# 05_LMS7002M_Misc.net
KiCad netlist of a schematic drawn in Altium Designer
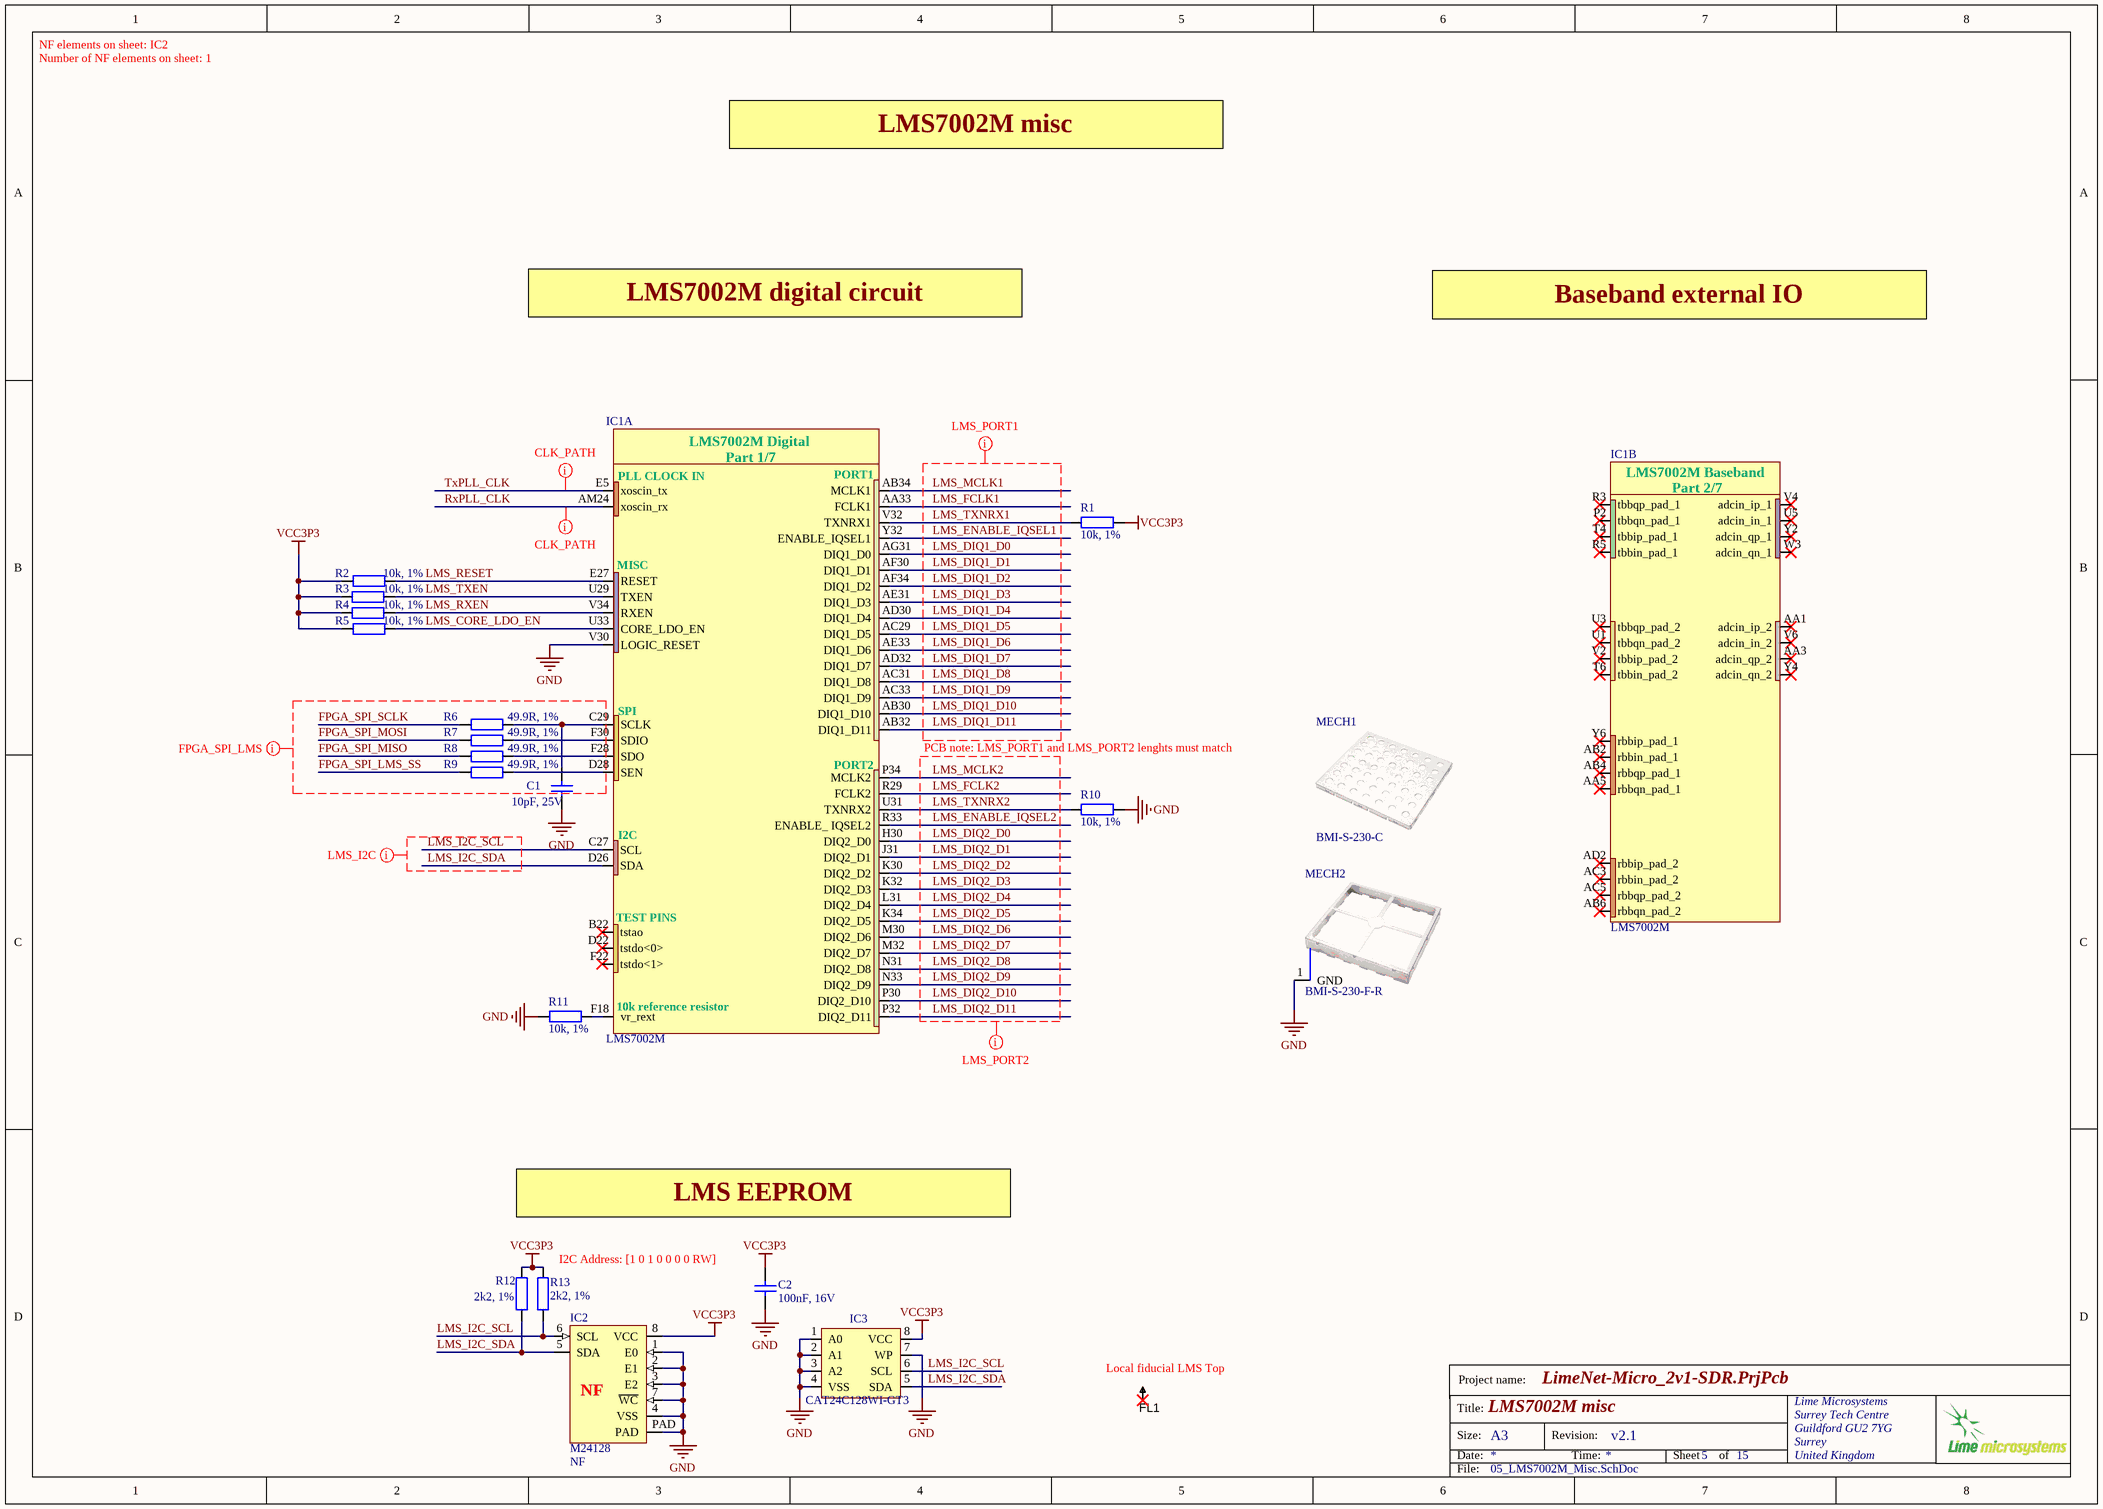
[diagram p0: 05_LMS7002M_Misc.SchDoc]

(export (version "E")
  (design (tool "Eeschema 10.0.6"))
  (components
    (comp (ref "C1")
      (value "10pF, 25V")
      (footprint "CAP0402")
      (fields (field (name "MANUFACTURER") "AVX"))
      (libsource (lib "LimeMicroAltiumLib_schLib") (part "Cap_0402"))
    )
    (comp (ref "C2")
      (value "100nF, 16V")
      (footprint "CAP0402")
      (fields (field (name "TOLERANCE") "10 %") (field (name "MANUFACTURER") "Murata Electronics"))
      (libsource (lib "LimeFPGAboard_schLib") (part "Cap_0603"))
    )
    (comp (ref "FL1")
      (value "Fiducial")
      (footprint "Fiducial_local")
      (libsource (lib "VGTU_Altium_lib") (part "Fiducial"))
    )
    (comp (ref "IC1")
      (value "LMS7002M")
      (footprint "LMS7002M_v5")
      (description "Schematic symbol revision 3. Default footprint - 0.31mm pad")
      (fields (field (name "MANUFACTURER") "Lime Microsystems"))
      (libsource (lib "LimeMicroAltiumLib_schLib") (part "LMS7002Mr3"))
    )
    (comp (ref "IC2")
      (value "M24128")
      (footprint "M24128-DFMC6TG")
      (fields (field (name "MANUFACTURER") "STMicroelectronics") (field (name "ASSEMBLY INFO") "NF"))
      (libsource (lib "LimeMicroAltiumLib_schLib") (part "M24128-DFMC6TG"))
    )
    (comp (ref "IC3")
      (value "CAT24C128WI-GT3")
      (footprint "SOIC127P600-8DL_v2")
      (fields (field (name "MANUFACTURER") "ON Semiconductor") (field (name "BASE PART NUMBER") "CAT24C128"))
      (libsource (lib "LimeMicroAltiumLib_schLib") (part "24FC64F"))
    )
    (comp (ref "MECH1")
      (value "BMI-S-230-C")
      (fields (field (name "MANUFACTURER") "Laird Technologies EMI"))
      (libsource (lib "LimeMicroAltiumLib_schLib_r01") (part "RFI_SHIELD_2_cover"))
    )
    (comp (ref "MECH2")
      (value "BMI-S-230-F-R")
      (footprint "RFI_SHIELD_BMI-S-230-F-R")
      (fields (field (name "MANUFACTURER") "Laird Technologies EMI"))
      (libsource (lib "LimeMicroAltiumLib_schLib_r01") (part "RFI_SHIELD_2_frame"))
    )
    (comp (ref "R1")
      (value "10k, 1%")
      (footprint "RES0402")
      (fields (field (name "MANUFACTURER") "Yageo") (field (name "TOLERANCE") "±1%"))
      (libsource (lib "LimeMicroAltiumLib_schLib") (part "Res_0402"))
    )
    (comp (ref "R2")
      (value "10k, 1%")
      (footprint "RES0402")
      (fields (field (name "MANUFACTURER") "Yageo") (field (name "TOLERANCE") "±1%"))
      (libsource (lib "LimeMicroAltiumLib_schLib") (part "Res_0402"))
    )
    (comp (ref "R3")
      (value "10k, 1%")
      (footprint "RES0402")
      (fields (field (name "MANUFACTURER") "Yageo") (field (name "TOLERANCE") "±1%"))
      (libsource (lib "LimeMicroAltiumLib_schLib") (part "Res_0402"))
    )
    (comp (ref "R4")
      (value "10k, 1%")
      (footprint "RES0402")
      (fields (field (name "MANUFACTURER") "Yageo") (field (name "TOLERANCE") "±1%"))
      (libsource (lib "LimeMicroAltiumLib_schLib") (part "Res_0402"))
    )
    (comp (ref "R5")
      (value "10k, 1%")
      (footprint "RES0402")
      (fields (field (name "MANUFACTURER") "Yageo") (field (name "TOLERANCE") "±1%"))
      (libsource (lib "LimeMicroAltiumLib_schLib") (part "Res_0402"))
    )
    (comp (ref "R6")
      (value "49.9R, 1%")
      (footprint "RES0402")
      (fields
        (field (name "TOLERANCE") "±1%")
        (field (name "MANUFACTURER") "Samsung Electro-Mechanics America, Inc.")
      )
      (libsource (lib "LimeMicroAltiumLib_schLib") (part "Res_0402"))
    )
    (comp (ref "R7")
      (value "49.9R, 1%")
      (footprint "RES0402")
      (fields
        (field (name "TOLERANCE") "±1%")
        (field (name "MANUFACTURER") "Samsung Electro-Mechanics America, Inc.")
      )
      (libsource (lib "LimeMicroAltiumLib_schLib") (part "Res_0402"))
    )
    (comp (ref "R8")
      (value "49.9R, 1%")
      (footprint "RES0402")
      (fields
        (field (name "TOLERANCE") "±1%")
        (field (name "MANUFACTURER") "Samsung Electro-Mechanics America, Inc.")
      )
      (libsource (lib "LimeMicroAltiumLib_schLib") (part "Res_0402"))
    )
    (comp (ref "R9")
      (value "49.9R, 1%")
      (footprint "RES0402")
      (fields
        (field (name "TOLERANCE") "±1%")
        (field (name "MANUFACTURER") "Samsung Electro-Mechanics America, Inc.")
      )
      (libsource (lib "LimeMicroAltiumLib_schLib") (part "Res_0402"))
    )
    (comp (ref "R10")
      (value "10k, 1%")
      (footprint "RES0402")
      (fields (field (name "MANUFACTURER") "Yageo") (field (name "TOLERANCE") "±1%"))
      (libsource (lib "LimeMicroAltiumLib_schLib") (part "Res_0402"))
    )
    (comp (ref "R11")
      (value "10k, 1%")
      (footprint "RES0402")
      (fields (field (name "MANUFACTURER") "Yageo") (field (name "TOLERANCE") "±1%"))
      (libsource (lib "LimeMicroAltiumLib_schLib") (part "Res_0402"))
    )
    (comp (ref "R12")
      (value "2k2, 1%")
      (footprint "RES0402")
      (fields (field (name "MANUFACTURER") "Stackpole Electronics Inc") (field (name "TOLERANCE") "±1%"))
      (libsource (lib "LimeMicroAltiumLib_schLib") (part "Res_0402"))
    )
    (comp (ref "R13")
      (value "2k2, 1%")
      (footprint "RES0402")
      (fields (field (name "MANUFACTURER") "Stackpole Electronics Inc") (field (name "TOLERANCE") "±1%"))
      (libsource (lib "LimeMicroAltiumLib_schLib") (part "Res_0402"))
    )
  )
  (nets
    (net (code "1") (name "/FPGA_SPI_LMS_SS") (class "Default")
      (node (ref "R9") (pin "2") (pinfunction "2_2") (pintype "passive"))
    )
    (net (code "2") (name "/FPGA_SPI_MISO") (class "Default")
      (node (ref "R8") (pin "2") (pinfunction "2_2") (pintype "passive"))
    )
    (net (code "3") (name "/FPGA_SPI_MOSI") (class "Default")
      (node (ref "R7") (pin "2") (pinfunction "2_2") (pintype "passive"))
    )
    (net (code "4") (name "/FPGA_SPI_SCLK") (class "Default")
      (node (ref "R6") (pin "2") (pinfunction "2_2") (pintype "passive"))
    )
    (net (code "5") (name "/LMS_CORE_LDO_EN") (class "Default")
      (node (ref "IC1") (pin "U33") (pinfunction "CORE_LDO_EN_U33") (pintype "passive"))
      (node (ref "R5") (pin "1") (pinfunction "1_1") (pintype "passive"))
    )
    (net (code "6") (name "/LMS_DIQ1_D0") (class "Default")
      (node (ref "IC1") (pin "AG31") (pinfunction "DIQ1_D0_AG31") (pintype "passive"))
    )
    (net (code "7") (name "/LMS_DIQ1_D1") (class "Default")
      (node (ref "IC1") (pin "AF30") (pinfunction "DIQ1_D1_AF30") (pintype "passive"))
    )
    (net (code "8") (name "/LMS_DIQ1_D2") (class "Default")
      (node (ref "IC1") (pin "AF34") (pinfunction "DIQ1_D2_AF34") (pintype "passive"))
    )
    (net (code "9") (name "/LMS_DIQ1_D3") (class "Default")
      (node (ref "IC1") (pin "AE31") (pinfunction "DIQ1_D3_AE31") (pintype "passive"))
    )
    (net (code "10") (name "/LMS_DIQ1_D4") (class "Default")
      (node (ref "IC1") (pin "AD30") (pinfunction "DIQ1_D4_AD30") (pintype "passive"))
    )
    (net (code "11") (name "/LMS_DIQ1_D5") (class "Default")
      (node (ref "IC1") (pin "AC29") (pinfunction "DIQ1_D5_AC29") (pintype "passive"))
    )
    (net (code "12") (name "/LMS_DIQ1_D6") (class "Default")
      (node (ref "IC1") (pin "AE33") (pinfunction "DIQ1_D6_AE33") (pintype "passive"))
    )
    (net (code "13") (name "/LMS_DIQ1_D7") (class "Default")
      (node (ref "IC1") (pin "AD32") (pinfunction "DIQ1_D7_AD32") (pintype "passive"))
    )
    (net (code "14") (name "/LMS_DIQ1_D8") (class "Default")
      (node (ref "IC1") (pin "AC31") (pinfunction "DIQ1_D8_AC31") (pintype "passive"))
    )
    (net (code "15") (name "/LMS_DIQ1_D9") (class "Default")
      (node (ref "IC1") (pin "AC33") (pinfunction "DIQ1_D9_AC33") (pintype "passive"))
    )
    (net (code "16") (name "/LMS_DIQ1_D10") (class "Default")
      (node (ref "IC1") (pin "AB30") (pinfunction "DIQ1_D10_AB30") (pintype "passive"))
    )
    (net (code "17") (name "/LMS_DIQ1_D11") (class "Default")
      (node (ref "IC1") (pin "AB32") (pinfunction "DIQ1_D11_AB32") (pintype "passive"))
    )
    (net (code "18") (name "/LMS_DIQ2_D0") (class "Default")
      (node (ref "IC1") (pin "H30") (pinfunction "DIQ2_D0_H30") (pintype "passive"))
    )
    (net (code "19") (name "/LMS_DIQ2_D1") (class "Default")
      (node (ref "IC1") (pin "J31") (pinfunction "DIQ2_D1_J31") (pintype "passive"))
    )
    (net (code "20") (name "/LMS_DIQ2_D2") (class "Default")
      (node (ref "IC1") (pin "K30") (pinfunction "DIQ2_D2_K30") (pintype "passive"))
    )
    (net (code "21") (name "/LMS_DIQ2_D3") (class "Default")
      (node (ref "IC1") (pin "K32") (pinfunction "DIQ2_D3_K32") (pintype "passive"))
    )
    (net (code "22") (name "/LMS_DIQ2_D4") (class "Default")
      (node (ref "IC1") (pin "L31") (pinfunction "DIQ2_D4_L31") (pintype "passive"))
    )
    (net (code "23") (name "/LMS_DIQ2_D5") (class "Default")
      (node (ref "IC1") (pin "K34") (pinfunction "DIQ2_D5_K34") (pintype "passive"))
    )
    (net (code "24") (name "/LMS_DIQ2_D6") (class "Default")
      (node (ref "IC1") (pin "M30") (pinfunction "DIQ2_D6_M30") (pintype "passive"))
    )
    (net (code "25") (name "/LMS_DIQ2_D7") (class "Default")
      (node (ref "IC1") (pin "M32") (pinfunction "DIQ2_D7_M32") (pintype "passive"))
    )
    (net (code "26") (name "/LMS_DIQ2_D8") (class "Default")
      (node (ref "IC1") (pin "N31") (pinfunction "DIQ2_D8_N31") (pintype "passive"))
    )
    (net (code "27") (name "/LMS_DIQ2_D9") (class "Default")
      (node (ref "IC1") (pin "N33") (pinfunction "DIQ2_D9_N33") (pintype "passive"))
    )
    (net (code "28") (name "/LMS_DIQ2_D10") (class "Default")
      (node (ref "IC1") (pin "P30") (pinfunction "DIQ2_D10_P30") (pintype "passive"))
    )
    (net (code "29") (name "/LMS_DIQ2_D11") (class "Default")
      (node (ref "IC1") (pin "P32") (pinfunction "DIQ2_D11_P32") (pintype "passive"))
    )
    (net (code "30") (name "/LMS_ENABLE_IQSEL1") (class "Default")
      (node (ref "IC1") (pin "Y32") (pinfunction "ENABLE_IQSEL1_Y32") (pintype "passive"))
    )
    (net (code "31") (name "/LMS_ENABLE_IQSEL2") (class "Default")
      (node (ref "IC1") (pin "R33") (pinfunction "ENABLE__IQSEL2_R33") (pintype "passive"))
    )
    (net (code "32") (name "/LMS_FCLK1") (class "Default")
      (node (ref "IC1") (pin "AA33") (pinfunction "FCLK1_AA33") (pintype "passive"))
    )
    (net (code "33") (name "/LMS_FCLK2") (class "Default")
      (node (ref "IC1") (pin "R29") (pinfunction "FCLK2_R29") (pintype "passive"))
    )
    (net (code "34") (name "/LMS_I2C_SCL") (class "Default")
      (node (ref "IC1") (pin "C27") (pinfunction "SCL_C27") (pintype "passive"))
      (node (ref "IC2") (pin "6") (pinfunction "SCL_6") (pintype "input"))
      (node (ref "IC3") (pin "6") (pinfunction "SCL_6") (pintype "passive"))
      (node (ref "R13") (pin "2") (pinfunction "2_2") (pintype "passive"))
    )
    (net (code "35") (name "/LMS_I2C_SDA") (class "Default")
      (node (ref "IC1") (pin "D26") (pinfunction "SDA_D26") (pintype "passive"))
      (node (ref "IC2") (pin "5") (pinfunction "SDA_5") (pintype "bidirectional"))
      (node (ref "IC3") (pin "5") (pinfunction "SDA_5") (pintype "passive"))
      (node (ref "R12") (pin "2") (pinfunction "2_2") (pintype "passive"))
    )
    (net (code "36") (name "/LMS_MCLK1") (class "Default")
      (node (ref "IC1") (pin "AB34") (pinfunction "MCLK1_AB34") (pintype "passive"))
    )
    (net (code "37") (name "/LMS_MCLK2") (class "Default")
      (node (ref "IC1") (pin "P34") (pinfunction "MCLK2_P34") (pintype "passive"))
    )
    (net (code "38") (name "/LMS_RESET") (class "Default")
      (node (ref "IC1") (pin "E27") (pinfunction "RESET_E27") (pintype "passive"))
      (node (ref "R2") (pin "1") (pinfunction "1_1") (pintype "passive"))
    )
    (net (code "39") (name "/LMS_RXEN") (class "Default")
      (node (ref "IC1") (pin "V34") (pinfunction "RXEN_V34") (pintype "passive"))
      (node (ref "R4") (pin "2") (pinfunction "2_2") (pintype "passive"))
    )
    (net (code "40") (name "/LMS_TXEN") (class "Default")
      (node (ref "IC1") (pin "U29") (pinfunction "TXEN_U29") (pintype "passive"))
      (node (ref "R3") (pin "2") (pinfunction "2_2") (pintype "passive"))
    )
    (net (code "41") (name "/LMS_TXNRX1") (class "Default")
      (node (ref "IC1") (pin "V32") (pinfunction "TXNRX1_V32") (pintype "passive"))
      (node (ref "R1") (pin "1") (pinfunction "1_1") (pintype "passive"))
    )
    (net (code "42") (name "/LMS_TXNRX2") (class "Default")
      (node (ref "IC1") (pin "U31") (pinfunction "TXNRX2_U31") (pintype "passive"))
      (node (ref "R10") (pin "1") (pinfunction "1_1") (pintype "passive"))
    )
    (net (code "43") (name "/RxPLL_CLK") (class "Default")
      (node (ref "IC1") (pin "AM24") (pinfunction "xoscin_rx_AM24") (pintype "passive"))
    )
    (net (code "44") (name "/TxPLL_CLK") (class "Default")
      (node (ref "IC1") (pin "E5") (pinfunction "xoscin_tx_E5") (pintype "passive"))
    )
    (net (code "45") (name "GND") (class "Default")
      (node (ref "C1") (pin "2") (pinfunction "2_2") (pintype "passive"))
      (node (ref "C2") (pin "2") (pinfunction "2_2") (pintype "passive"))
      (node (ref "IC1") (pin "V30") (pinfunction "LOGIC_RESET_V30") (pintype "passive"))
      (node (ref "IC2") (pin "1") (pinfunction "E0_1") (pintype "input"))
      (node (ref "IC2") (pin "2") (pinfunction "E1_2") (pintype "input"))
      (node (ref "IC2") (pin "3") (pinfunction "E2_3") (pintype "input"))
      (node (ref "IC2") (pin "4") (pinfunction "VSS_4") (pintype "power_in"))
      (node (ref "IC2") (pin "7") (pinfunction "~{WC}_7") (pintype "input"))
      (node (ref "IC2") (pin "PAD") (pinfunction "PAD_PAD") (pintype "power_in"))
      (node (ref "IC3") (pin "1") (pinfunction "A0_1") (pintype "passive"))
      (node (ref "IC3") (pin "2") (pinfunction "A1_2") (pintype "passive"))
      (node (ref "IC3") (pin "3") (pinfunction "A2_3") (pintype "passive"))
      (node (ref "IC3") (pin "4") (pinfunction "VSS_4") (pintype "passive"))
      (node (ref "IC3") (pin "7") (pinfunction "WP_7") (pintype "passive"))
      (node (ref "MECH2") (pin "1") (pinfunction "GND_1") (pintype "passive"))
      (node (ref "R10") (pin "2") (pinfunction "2_2") (pintype "passive"))
      (node (ref "R11") (pin "2") (pinfunction "2_2") (pintype "passive"))
    )
    (net (code "46") (name "Net-(IC1A-SCLK)") (class "Default")
      (node (ref "C1") (pin "1") (pinfunction "1_1") (pintype "passive"))
      (node (ref "IC1") (pin "C29") (pinfunction "SCLK_C29") (pintype "passive"))
      (node (ref "R6") (pin "1") (pinfunction "1_1") (pintype "passive"))
    )
    (net (code "47") (name "Net-(IC1A-SDIO)") (class "Default")
      (node (ref "IC1") (pin "F30") (pinfunction "SDIO_F30") (pintype "passive"))
      (node (ref "R7") (pin "1") (pinfunction "1_1") (pintype "passive"))
    )
    (net (code "48") (name "Net-(IC1A-SDO)") (class "Default")
      (node (ref "IC1") (pin "F28") (pinfunction "SDO_F28") (pintype "passive"))
      (node (ref "R8") (pin "1") (pinfunction "1_1") (pintype "passive"))
    )
    (net (code "49") (name "Net-(IC1A-SEN)") (class "Default")
      (node (ref "IC1") (pin "D28") (pinfunction "SEN_D28") (pintype "passive"))
      (node (ref "R9") (pin "1") (pinfunction "1_1") (pintype "passive"))
    )
    (net (code "50") (name "Net-(IC1A-vr_rext)") (class "Default")
      (node (ref "IC1") (pin "F18") (pinfunction "vr_rext_F18") (pintype "passive"))
      (node (ref "R11") (pin "1") (pinfunction "1_1") (pintype "passive"))
    )
    (net (code "51") (name "VCC3P3") (class "Default")
      (node (ref "C2") (pin "1") (pinfunction "1_1") (pintype "passive"))
      (node (ref "IC2") (pin "8") (pinfunction "VCC_8") (pintype "power_in"))
      (node (ref "IC3") (pin "8") (pinfunction "VCC_8") (pintype "passive"))
      (node (ref "R1") (pin "2") (pinfunction "2_2") (pintype "passive"))
      (node (ref "R12") (pin "1") (pinfunction "1_1") (pintype "passive"))
      (node (ref "R13") (pin "1") (pinfunction "1_1") (pintype "passive"))
      (node (ref "R2") (pin "2") (pinfunction "2_2") (pintype "passive"))
      (node (ref "R3") (pin "1") (pinfunction "1_1") (pintype "passive"))
      (node (ref "R4") (pin "1") (pinfunction "1_1") (pintype "passive"))
      (node (ref "R5") (pin "2") (pinfunction "2_2") (pintype "passive"))
    )
    (net (code "52") (name "unconnected-(FL1-Pad1)") (class "Default")
      (node (ref "FL1") (pin "1") (pintype "passive+no_connect"))
    )
    (net (code "53") (name "unconnected-(IC1A-tstao-PadB22)") (class "Default")
      (node (ref "IC1") (pin "B22") (pinfunction "tstao_B22") (pintype "passive+no_connect"))
    )
    (net (code "54") (name "unconnected-(IC1A-tstdo<0>-PadD22)") (class "Default")
      (node (ref "IC1") (pin "D22") (pinfunction "tstdo<0>_D22") (pintype "passive+no_connect"))
    )
    (net (code "55") (name "unconnected-(IC1A-tstdo<1>-PadF22)") (class "Default")
      (node (ref "IC1") (pin "F22") (pinfunction "tstdo<1>_F22") (pintype "passive+no_connect"))
    )
    (net (code "56") (name "unconnected-(IC1B-adcin_in_1-PadU5)") (class "Default")
      (node (ref "IC1") (pin "U5") (pinfunction "adcin_in_1_U5") (pintype "passive+no_connect"))
    )
    (net (code "57") (name "unconnected-(IC1B-adcin_in_2-PadV6)") (class "Default")
      (node (ref "IC1") (pin "V6") (pinfunction "adcin_in_2_V6") (pintype "passive+no_connect"))
    )
    (net (code "58") (name "unconnected-(IC1B-adcin_ip_1-PadV4)") (class "Default")
      (node (ref "IC1") (pin "V4") (pinfunction "adcin_ip_1_V4") (pintype "passive+no_connect"))
    )
    (net (code "59") (name "unconnected-(IC1B-adcin_ip_2-PadAA1)") (class "Default")
      (node (ref "IC1") (pin "AA1") (pinfunction "adcin_ip_2_AA1") (pintype "passive+no_connect"))
    )
    (net (code "60") (name "unconnected-(IC1B-adcin_qn_1-PadW3)") (class "Default")
      (node (ref "IC1") (pin "W3") (pinfunction "adcin_qn_1_W3") (pintype "passive+no_connect"))
    )
    (net (code "61") (name "unconnected-(IC1B-adcin_qn_2-PadY4)") (class "Default")
      (node (ref "IC1") (pin "Y4") (pinfunction "adcin_qn_2_Y4") (pintype "passive+no_connect"))
    )
    (net (code "62") (name "unconnected-(IC1B-adcin_qp_1-PadY2)") (class "Default")
      (node (ref "IC1") (pin "Y2") (pinfunction "adcin_qp_1_Y2") (pintype "passive+no_connect"))
    )
    (net (code "63") (name "unconnected-(IC1B-adcin_qp_2-PadAA3)") (class "Default")
      (node (ref "IC1") (pin "AA3") (pinfunction "adcin_qp_2_AA3") (pintype "passive+no_connect"))
    )
    (net (code "64") (name "unconnected-(IC1B-rbbin_pad_1-PadAB2)") (class "Default")
      (node (ref "IC1") (pin "AB2") (pinfunction "rbbin_pad_1_AB2") (pintype "passive+no_connect"))
    )
    (net (code "65") (name "unconnected-(IC1B-rbbin_pad_2-PadAC3)") (class "Default")
      (node (ref "IC1") (pin "AC3") (pinfunction "rbbin_pad_2_AC3") (pintype "passive+no_connect"))
    )
    (net (code "66") (name "unconnected-(IC1B-rbbip_pad_1-PadY6)") (class "Default")
      (node (ref "IC1") (pin "Y6") (pinfunction "rbbip_pad_1_Y6") (pintype "passive+no_connect"))
    )
    (net (code "67") (name "unconnected-(IC1B-rbbip_pad_2-PadAD2)") (class "Default")
      (node (ref "IC1") (pin "AD2") (pinfunction "rbbip_pad_2_AD2") (pintype "passive+no_connect"))
    )
    (net (code "68") (name "unconnected-(IC1B-rbbqn_pad_1-PadAA5)") (class "Default")
      (node (ref "IC1") (pin "AA5") (pinfunction "rbbqn_pad_1_AA5") (pintype "passive+no_connect"))
    )
    (net (code "69") (name "unconnected-(IC1B-rbbqn_pad_2-PadAB6)") (class "Default")
      (node (ref "IC1") (pin "AB6") (pinfunction "rbbqn_pad_2_AB6") (pintype "passive+no_connect"))
    )
    (net (code "70") (name "unconnected-(IC1B-rbbqp_pad_1-PadAB4)") (class "Default")
      (node (ref "IC1") (pin "AB4") (pinfunction "rbbqp_pad_1_AB4") (pintype "passive+no_connect"))
    )
    (net (code "71") (name "unconnected-(IC1B-rbbqp_pad_2-PadAC5)") (class "Default")
      (node (ref "IC1") (pin "AC5") (pinfunction "rbbqp_pad_2_AC5") (pintype "passive+no_connect"))
    )
    (net (code "72") (name "unconnected-(IC1B-tbbin_pad_1-PadR5)") (class "Default")
      (node (ref "IC1") (pin "R5") (pinfunction "tbbin_pad_1_R5") (pintype "passive+no_connect"))
    )
    (net (code "73") (name "unconnected-(IC1B-tbbin_pad_2-PadT6)") (class "Default")
      (node (ref "IC1") (pin "T6") (pinfunction "tbbin_pad_2_T6") (pintype "passive+no_connect"))
    )
    (net (code "74") (name "unconnected-(IC1B-tbbip_pad_1-PadT4)") (class "Default")
      (node (ref "IC1") (pin "T4") (pinfunction "tbbip_pad_1_T4") (pintype "passive+no_connect"))
    )
    (net (code "75") (name "unconnected-(IC1B-tbbip_pad_2-PadV2)") (class "Default")
      (node (ref "IC1") (pin "V2") (pinfunction "tbbip_pad_2_V2") (pintype "passive+no_connect"))
    )
    (net (code "76") (name "unconnected-(IC1B-tbbqn_pad_1-PadP2)") (class "Default")
      (node (ref "IC1") (pin "P2") (pinfunction "tbbqn_pad_1_P2") (pintype "passive+no_connect"))
    )
    (net (code "77") (name "unconnected-(IC1B-tbbqn_pad_2-PadU1)") (class "Default")
      (node (ref "IC1") (pin "U1") (pinfunction "tbbqn_pad_2_U1") (pintype "passive+no_connect"))
    )
    (net (code "78") (name "unconnected-(IC1B-tbbqp_pad_1-PadR3)") (class "Default")
      (node (ref "IC1") (pin "R3") (pinfunction "tbbqp_pad_1_R3") (pintype "passive+no_connect"))
    )
    (net (code "79") (name "unconnected-(IC1B-tbbqp_pad_2-PadU3)") (class "Default")
      (node (ref "IC1") (pin "U3") (pinfunction "tbbqp_pad_2_U3") (pintype "passive+no_connect"))
    )
  )
)
